# ProgrammableOLED.net
KiCad netlist of a schematic drawn in EAGLE
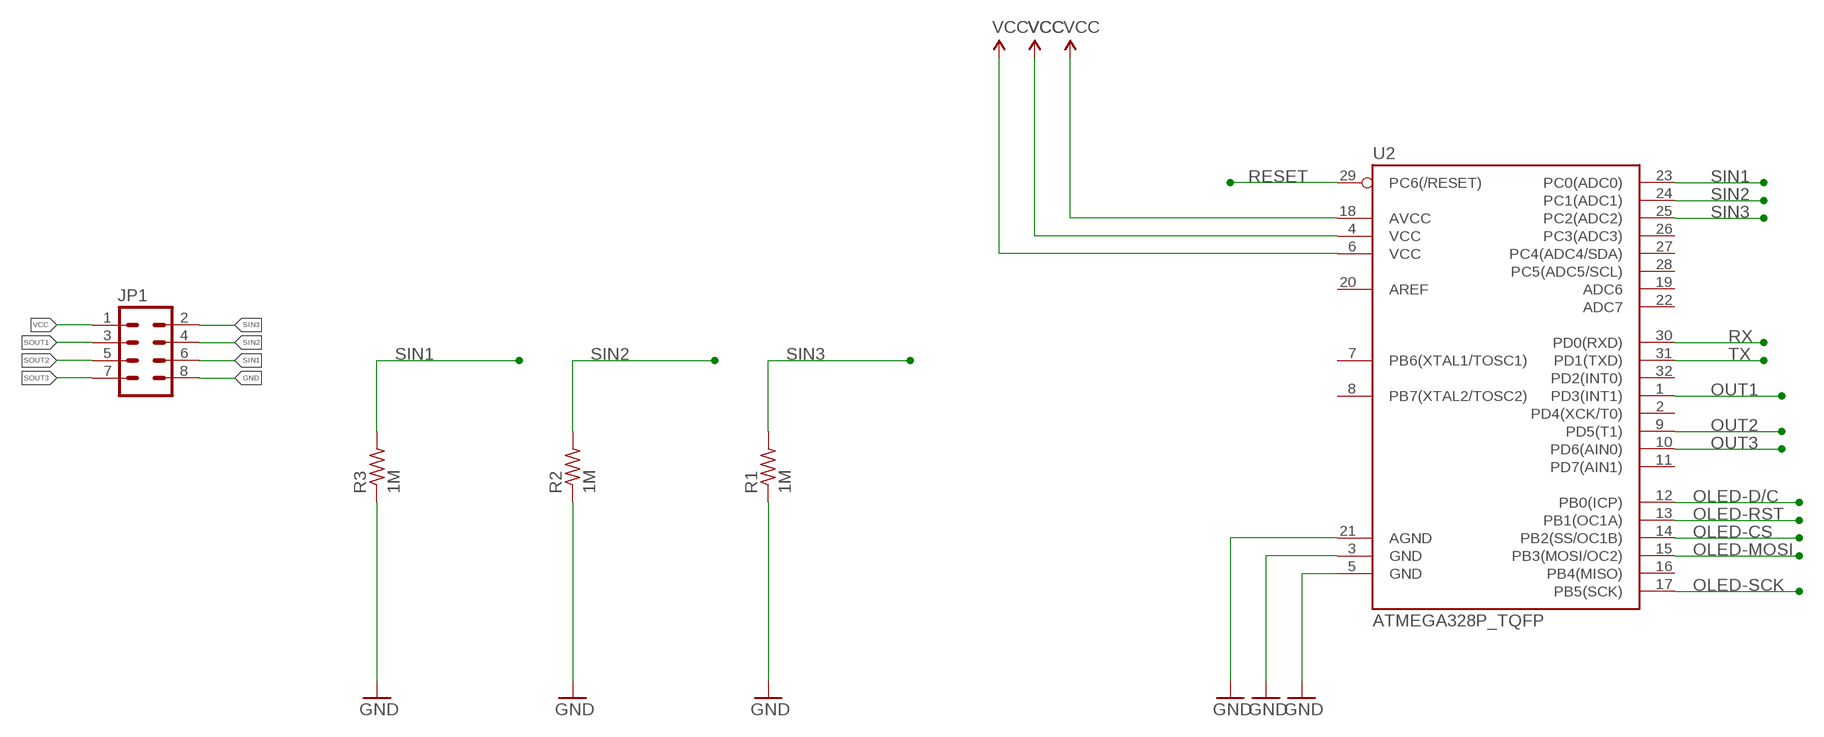
[diagram p0: schematic, sheet 1, part 1 of 2]
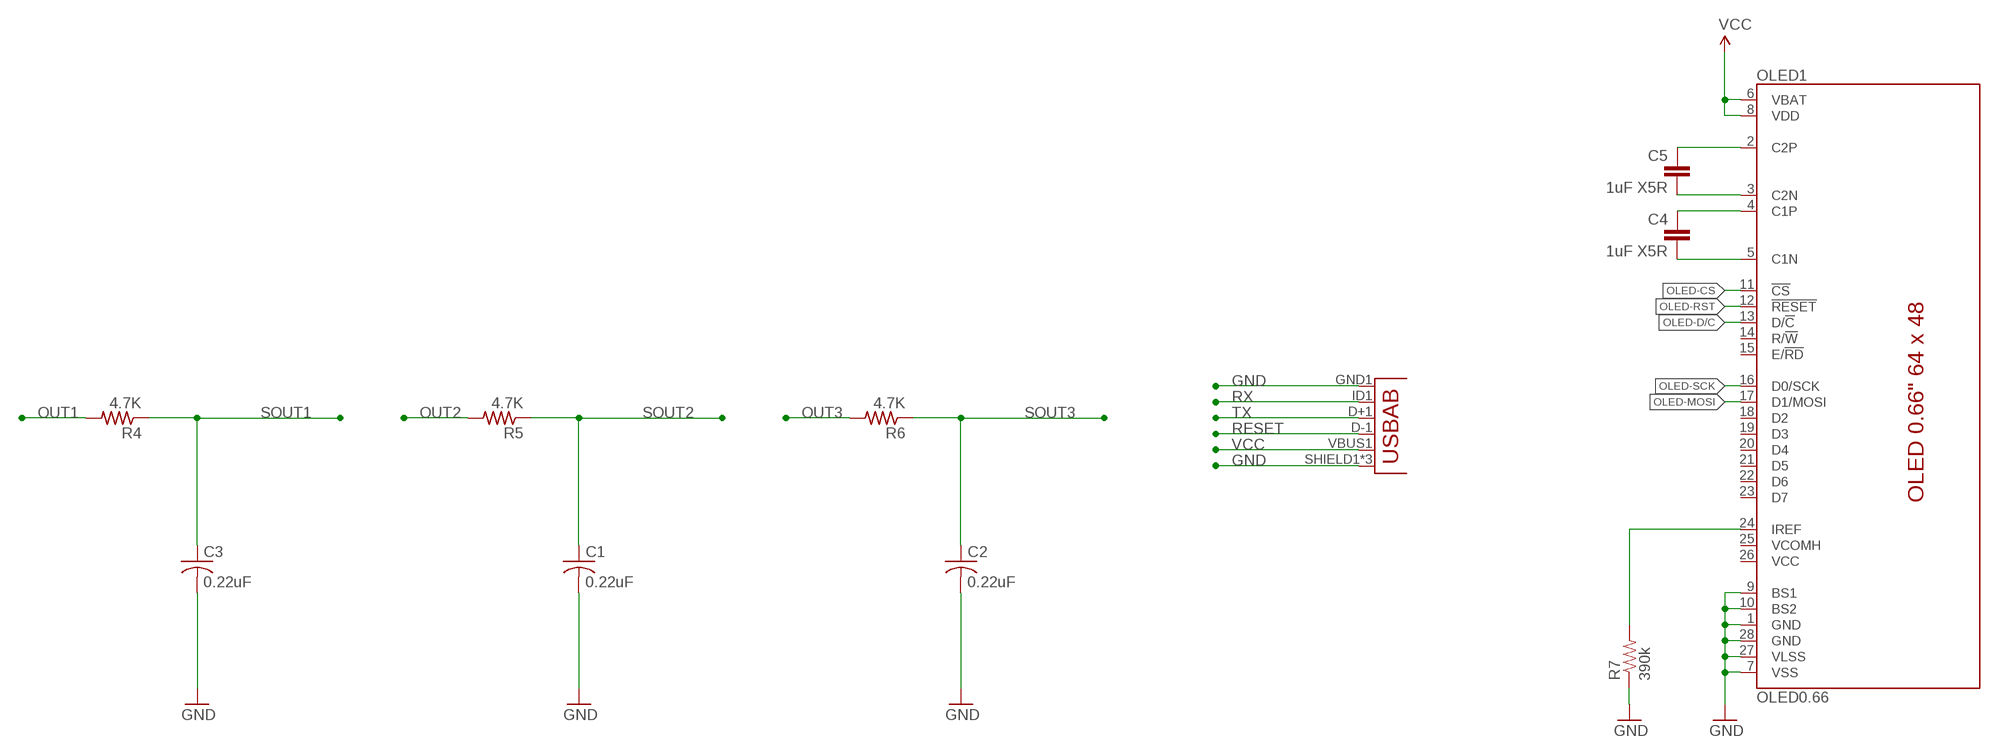
[diagram p1: schematic, sheet 1, part 2 of 2]

(export (version "E")
  (design (tool "Eeschema 10.0.6"))
  (components
    (comp (ref "C1")
      (value "0.22uF")
      (footprint "eagle-import:C0603")
      (libsource (lib "eagle-import") (part "C-USC0603"))
    )
    (comp (ref "C2")
      (value "0.22uF")
      (footprint "eagle-import:C0603")
      (libsource (lib "eagle-import") (part "C-USC0603"))
    )
    (comp (ref "C3")
      (value "0.22uF")
      (footprint "eagle-import:C0603")
      (libsource (lib "eagle-import") (part "C-USC0603"))
    )
    (comp (ref "C4")
      (value "1uF X5R")
      (footprint "eagle-import:0805")
      (libsource (lib "eagle-import") (part "CAP0805"))
    )
    (comp (ref "C5")
      (value "1uF X5R")
      (footprint "eagle-import:0805")
      (libsource (lib "eagle-import") (part "CAP0805"))
    )
    (comp (ref "JP1")
      (value "M04X2")
      (footprint "eagle-import:2X4")
      (libsource (lib "eagle-import") (part "M04X2"))
    )
    (comp (ref "JP5")
      (value "USB-ABCONN-11794")
      (footprint "eagle-import:USB-AB-MICRO-SMD_V03")
      (libsource (lib "eagle-import") (part "USB-ABCONN-11794"))
    )
    (comp (ref "OLED1")
      (value "OLED0.66")
      (footprint "eagle-import:OLED-0.66-64X48")
      (libsource (lib "eagle-import") (part "OLED0.66"))
    )
    (comp (ref "R1")
      (value "1M")
      (footprint "eagle-import:R0603")
      (libsource (lib "eagle-import") (part "R-US_R0603"))
    )
    (comp (ref "R2")
      (value "1M")
      (footprint "eagle-import:R0603")
      (libsource (lib "eagle-import") (part "R-US_R0603"))
    )
    (comp (ref "R3")
      (value "1M")
      (footprint "eagle-import:R0603")
      (libsource (lib "eagle-import") (part "R-US_R0603"))
    )
    (comp (ref "R4")
      (value "4.7K")
      (footprint "eagle-import:R0603")
      (libsource (lib "eagle-import") (part "R-US_R0603"))
    )
    (comp (ref "R5")
      (value "4.7K")
      (footprint "eagle-import:R0603")
      (libsource (lib "eagle-import") (part "R-US_R0603"))
    )
    (comp (ref "R6")
      (value "4.7K")
      (footprint "eagle-import:R0603")
      (libsource (lib "eagle-import") (part "R-US_R0603"))
    )
    (comp (ref "R7")
      (value "390k")
      (footprint "eagle-import:0603-RES")
      (libsource (lib "eagle-import") (part "RESISTOR0603-RES"))
    )
    (comp (ref "U2")
      (value "ATMEGA328P_TQFP")
      (footprint "eagle-import:TQFP32-08")
      (libsource (lib "eagle-import") (part "ATMEGA328P_TQFP"))
    )
  )
  (nets
    (net (code "1") (name "/OUT1") (class "Default")
      (node (ref "R4") (pin "2") (pinfunction "2_2") (pintype "passive"))
      (node (ref "U2") (pin "1") (pinfunction "PD3(INT1)_1") (pintype "bidirectional"))
    )
    (net (code "2") (name "/OUT2") (class "Default")
      (node (ref "R5") (pin "2") (pinfunction "2_2") (pintype "passive"))
      (node (ref "U2") (pin "9") (pinfunction "PD5(T1)_9") (pintype "bidirectional"))
    )
    (net (code "3") (name "/OUT3") (class "Default")
      (node (ref "R6") (pin "2") (pinfunction "2_2") (pintype "passive"))
      (node (ref "U2") (pin "10") (pinfunction "PD6(AIN0)_10") (pintype "bidirectional"))
    )
    (net (code "4") (name "/RESET") (class "Default")
      (node (ref "JP5") (pin "D-1") (pinfunction "D-_D-1") (pintype "bidirectional"))
      (node (ref "U2") (pin "29") (pinfunction "PC6(/RESET)_29") (pintype "bidirectional"))
    )
    (net (code "5") (name "/RX") (class "Default")
      (node (ref "JP5") (pin "ID1") (pinfunction "USBID_ID1") (pintype "bidirectional"))
      (node (ref "U2") (pin "30") (pinfunction "PD0(RXD)_30") (pintype "bidirectional"))
    )
    (net (code "6") (name "/TX") (class "Default")
      (node (ref "JP5") (pin "D+1") (pinfunction "D+_D+1") (pintype "bidirectional"))
      (node (ref "U2") (pin "31") (pinfunction "PD1(TXD)_31") (pintype "bidirectional"))
    )
    (net (code "7") (name "GND") (class "Default")
      (node (ref "C1") (pin "2") (pinfunction "2_2") (pintype "passive"))
      (node (ref "C2") (pin "2") (pinfunction "2_2") (pintype "passive"))
      (node (ref "C3") (pin "2") (pinfunction "2_2") (pintype "passive"))
      (node (ref "JP1") (pin "8") (pinfunction "8_8") (pintype "passive"))
      (node (ref "JP5") (pin "GND1") (pinfunction "GND_GND1") (pintype "bidirectional"))
      (node (ref "JP5") (pin "SHIELD1") (pinfunction "SHIELD_SHIELD1") (pintype "bidirectional"))
      (node (ref "JP5") (pin "SHIELD2") (pinfunction "SHIELD_SHIELD2") (pintype "bidirectional"))
      (node (ref "JP5") (pin "SHIELD3") (pinfunction "SHIELD_SHIELD3") (pintype "bidirectional"))
      (node (ref "OLED1") (pin "1") (pinfunction "GND_1") (pintype "bidirectional"))
      (node (ref "OLED1") (pin "10") (pinfunction "BS2_10") (pintype "bidirectional"))
      (node (ref "OLED1") (pin "27") (pinfunction "VLSS_27") (pintype "bidirectional"))
      (node (ref "OLED1") (pin "28") (pinfunction "GND_28") (pintype "bidirectional"))
      (node (ref "OLED1") (pin "7") (pinfunction "VSS_7") (pintype "bidirectional"))
      (node (ref "OLED1") (pin "9") (pinfunction "BS1_9") (pintype "bidirectional"))
      (node (ref "R1") (pin "1") (pinfunction "1_1") (pintype "passive"))
      (node (ref "R2") (pin "1") (pinfunction "1_1") (pintype "passive"))
      (node (ref "R3") (pin "1") (pinfunction "1_1") (pintype "passive"))
      (node (ref "R7") (pin "1") (pinfunction "1_1") (pintype "passive"))
      (node (ref "U2") (pin "21") (pinfunction "AGND_21") (pintype "bidirectional"))
      (node (ref "U2") (pin "3") (pinfunction "GND_3") (pintype "bidirectional"))
      (node (ref "U2") (pin "5") (pinfunction "GND_5") (pintype "bidirectional"))
    )
    (net (code "8") (name "Net-(OLED1-C1N)") (class "Default")
      (node (ref "C4") (pin "2") (pinfunction "2_2") (pintype "passive"))
      (node (ref "OLED1") (pin "5") (pinfunction "C1N_5") (pintype "bidirectional"))
    )
    (net (code "9") (name "Net-(OLED1-C1P)") (class "Default")
      (node (ref "C4") (pin "1") (pinfunction "1_1") (pintype "passive"))
      (node (ref "OLED1") (pin "4") (pinfunction "C1P_4") (pintype "bidirectional"))
    )
    (net (code "10") (name "Net-(OLED1-C2N)") (class "Default")
      (node (ref "C5") (pin "2") (pinfunction "2_2") (pintype "passive"))
      (node (ref "OLED1") (pin "3") (pinfunction "C2N_3") (pintype "bidirectional"))
    )
    (net (code "11") (name "Net-(OLED1-C2P)") (class "Default")
      (node (ref "C5") (pin "1") (pinfunction "1_1") (pintype "passive"))
      (node (ref "OLED1") (pin "2") (pinfunction "C2P_2") (pintype "bidirectional"))
    )
    (net (code "12") (name "Net-(OLED1-IREF)") (class "Default")
      (node (ref "OLED1") (pin "24") (pinfunction "IREF_24") (pintype "bidirectional"))
      (node (ref "R7") (pin "2") (pinfunction "2_2") (pintype "passive"))
    )
    (net (code "13") (name "OLED-CS") (class "Default")
      (node (ref "OLED1") (pin "11") (pinfunction "~{CS}_11") (pintype "bidirectional"))
      (node (ref "U2") (pin "14") (pinfunction "PB2(SS/OC1B)_14") (pintype "bidirectional"))
    )
    (net (code "14") (name "OLED-D{slash}C") (class "Default")
      (node (ref "OLED1") (pin "13") (pinfunction "D/~{C}_13") (pintype "bidirectional"))
      (node (ref "U2") (pin "12") (pinfunction "PB0(ICP)_12") (pintype "bidirectional"))
    )
    (net (code "15") (name "OLED-MOSI") (class "Default")
      (node (ref "OLED1") (pin "17") (pinfunction "D1/MOSI_17") (pintype "bidirectional"))
      (node (ref "U2") (pin "15") (pinfunction "PB3(MOSI/OC2)_15") (pintype "bidirectional"))
    )
    (net (code "16") (name "OLED-RST") (class "Default")
      (node (ref "OLED1") (pin "12") (pinfunction "~{RESET}_12") (pintype "bidirectional"))
      (node (ref "U2") (pin "13") (pinfunction "PB1(OC1A)_13") (pintype "bidirectional"))
    )
    (net (code "17") (name "OLED-SCK") (class "Default")
      (node (ref "OLED1") (pin "16") (pinfunction "D0/SCK_16") (pintype "bidirectional"))
      (node (ref "U2") (pin "17") (pinfunction "PB5(SCK)_17") (pintype "bidirectional"))
    )
    (net (code "18") (name "SIN1") (class "Default")
      (node (ref "JP1") (pin "6") (pinfunction "6_6") (pintype "passive"))
      (node (ref "R3") (pin "2") (pinfunction "2_2") (pintype "passive"))
      (node (ref "U2") (pin "23") (pinfunction "PC0(ADC0)_23") (pintype "bidirectional"))
    )
    (net (code "19") (name "SIN2") (class "Default")
      (node (ref "JP1") (pin "4") (pinfunction "4_4") (pintype "passive"))
      (node (ref "R2") (pin "2") (pinfunction "2_2") (pintype "passive"))
      (node (ref "U2") (pin "24") (pinfunction "PC1(ADC1)_24") (pintype "bidirectional"))
    )
    (net (code "20") (name "SIN3") (class "Default")
      (node (ref "JP1") (pin "2") (pinfunction "2_2") (pintype "passive"))
      (node (ref "R1") (pin "2") (pinfunction "2_2") (pintype "passive"))
      (node (ref "U2") (pin "25") (pinfunction "PC2(ADC2)_25") (pintype "bidirectional"))
    )
    (net (code "21") (name "SOUT1") (class "Default")
      (node (ref "C3") (pin "1") (pinfunction "1_1") (pintype "passive"))
      (node (ref "JP1") (pin "3") (pinfunction "3_3") (pintype "passive"))
      (node (ref "R4") (pin "1") (pinfunction "1_1") (pintype "passive"))
    )
    (net (code "22") (name "SOUT2") (class "Default")
      (node (ref "C1") (pin "1") (pinfunction "1_1") (pintype "passive"))
      (node (ref "JP1") (pin "5") (pinfunction "5_5") (pintype "passive"))
      (node (ref "R5") (pin "1") (pinfunction "1_1") (pintype "passive"))
    )
    (net (code "23") (name "SOUT3") (class "Default")
      (node (ref "C2") (pin "1") (pinfunction "1_1") (pintype "passive"))
      (node (ref "JP1") (pin "7") (pinfunction "7_7") (pintype "passive"))
      (node (ref "R6") (pin "1") (pinfunction "1_1") (pintype "passive"))
    )
    (net (code "24") (name "VCC") (class "Default")
      (node (ref "JP1") (pin "1") (pinfunction "1_1") (pintype "passive"))
      (node (ref "JP5") (pin "VBUS1") (pinfunction "VBUS_VBUS1") (pintype "bidirectional"))
      (node (ref "OLED1") (pin "6") (pinfunction "VBAT_6") (pintype "bidirectional"))
      (node (ref "OLED1") (pin "8") (pinfunction "VDD_8") (pintype "bidirectional"))
      (node (ref "U2") (pin "18") (pinfunction "AVCC_18") (pintype "bidirectional"))
      (node (ref "U2") (pin "4") (pinfunction "VCC_4") (pintype "bidirectional"))
      (node (ref "U2") (pin "6") (pinfunction "VCC_6") (pintype "bidirectional"))
    )
    (net (code "25") (name "unconnected-(OLED1-D2-Pad18)") (class "Default")
      (node (ref "OLED1") (pin "18") (pinfunction "D2_18") (pintype "bidirectional"))
    )
    (net (code "26") (name "unconnected-(OLED1-D3-Pad19)") (class "Default")
      (node (ref "OLED1") (pin "19") (pinfunction "D3_19") (pintype "bidirectional"))
    )
    (net (code "27") (name "unconnected-(OLED1-D4-Pad20)") (class "Default")
      (node (ref "OLED1") (pin "20") (pinfunction "D4_20") (pintype "bidirectional"))
    )
    (net (code "28") (name "unconnected-(OLED1-D5-Pad21)") (class "Default")
      (node (ref "OLED1") (pin "21") (pinfunction "D5_21") (pintype "bidirectional"))
    )
    (net (code "29") (name "unconnected-(OLED1-D6-Pad22)") (class "Default")
      (node (ref "OLED1") (pin "22") (pinfunction "D6_22") (pintype "bidirectional"))
    )
    (net (code "30") (name "unconnected-(OLED1-D7-Pad23)") (class "Default")
      (node (ref "OLED1") (pin "23") (pinfunction "D7_23") (pintype "bidirectional"))
    )
    (net (code "31") (name "unconnected-(OLED1-E{slash}~{RD}-Pad15)") (class "Default")
      (node (ref "OLED1") (pin "15") (pinfunction "E/~{RD}_15") (pintype "bidirectional"))
    )
    (net (code "32") (name "unconnected-(OLED1-R{slash}~{W}-Pad14)") (class "Default")
      (node (ref "OLED1") (pin "14") (pinfunction "R/~{W}_14") (pintype "bidirectional"))
    )
    (net (code "33") (name "unconnected-(OLED1-VCC-Pad26)") (class "Default")
      (node (ref "OLED1") (pin "26") (pinfunction "VCC_26") (pintype "bidirectional"))
    )
    (net (code "34") (name "unconnected-(OLED1-VCOMH-Pad25)") (class "Default")
      (node (ref "OLED1") (pin "25") (pinfunction "VCOMH_25") (pintype "bidirectional"))
    )
    (net (code "35") (name "unconnected-(U2-ADC6-Pad19)") (class "Default")
      (node (ref "U2") (pin "19") (pinfunction "ADC6_19") (pintype "bidirectional"))
    )
    (net (code "36") (name "unconnected-(U2-ADC7-Pad22)") (class "Default")
      (node (ref "U2") (pin "22") (pinfunction "ADC7_22") (pintype "bidirectional"))
    )
    (net (code "37") (name "unconnected-(U2-AREF-Pad20)") (class "Default")
      (node (ref "U2") (pin "20") (pinfunction "AREF_20") (pintype "bidirectional"))
    )
    (net (code "38") (name "unconnected-(U2-PB4(MISO)-Pad16)") (class "Default")
      (node (ref "U2") (pin "16") (pinfunction "PB4(MISO)_16") (pintype "bidirectional"))
    )
    (net (code "39") (name "unconnected-(U2-PB6(XTAL1{slash}TOSC1)-Pad7)") (class "Default")
      (node (ref "U2") (pin "7") (pinfunction "PB6(XTAL1/TOSC1)_7") (pintype "bidirectional"))
    )
    (net (code "40") (name "unconnected-(U2-PB7(XTAL2{slash}TOSC2)-Pad8)") (class "Default")
      (node (ref "U2") (pin "8") (pinfunction "PB7(XTAL2/TOSC2)_8") (pintype "bidirectional"))
    )
    (net (code "41") (name "unconnected-(U2-PC3(ADC3)-Pad26)") (class "Default")
      (node (ref "U2") (pin "26") (pinfunction "PC3(ADC3)_26") (pintype "bidirectional"))
    )
    (net (code "42") (name "unconnected-(U2-PC4(ADC4{slash}SDA)-Pad27)") (class "Default")
      (node (ref "U2") (pin "27") (pinfunction "PC4(ADC4/SDA)_27") (pintype "bidirectional"))
    )
    (net (code "43") (name "unconnected-(U2-PC5(ADC5{slash}SCL)-Pad28)") (class "Default")
      (node (ref "U2") (pin "28") (pinfunction "PC5(ADC5/SCL)_28") (pintype "bidirectional"))
    )
    (net (code "44") (name "unconnected-(U2-PD2(INT0)-Pad32)") (class "Default")
      (node (ref "U2") (pin "32") (pinfunction "PD2(INT0)_32") (pintype "bidirectional"))
    )
    (net (code "45") (name "unconnected-(U2-PD4(XCK{slash}T0)-Pad2)") (class "Default")
      (node (ref "U2") (pin "2") (pinfunction "PD4(XCK/T0)_2") (pintype "bidirectional"))
    )
    (net (code "46") (name "unconnected-(U2-PD7(AIN1)-Pad11)") (class "Default")
      (node (ref "U2") (pin "11") (pinfunction "PD7(AIN1)_11") (pintype "bidirectional"))
    )
  )
)
